# 2_interface.net
KiCad netlist of a schematic drawn in Altium Designer
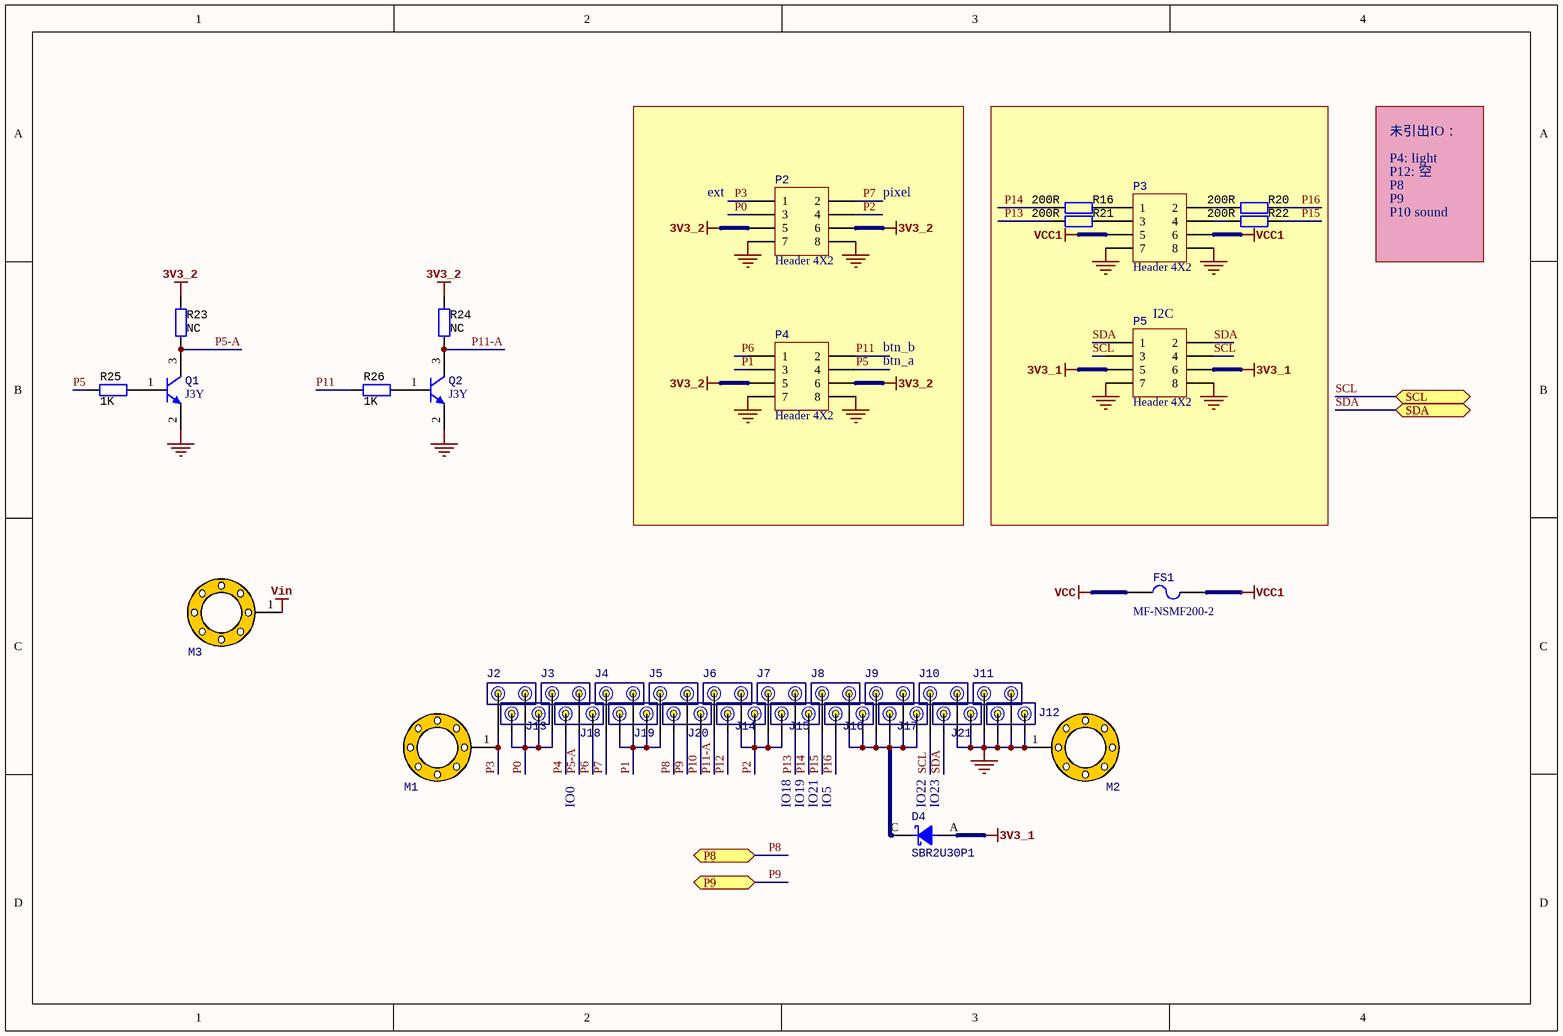
[diagram p0: 2.interface.SchDoc]

(export (version "E")
  (design (tool "Eeschema 10.0.6"))
  (components
    (comp (ref "D4")
      (value "SBR2U30P1")
      (footprint "POWERDI123")
      (fields (field (name "PARTNUMBER") "?") (field (name "PUBLISHER") "Altium Limited"))
      (libsource (lib "03.常用器件") (part "Diode_Schottky"))
    )
    (comp (ref "FS1")
      (value "MF-NSMF200-2")
      (footprint "R1206")
      (description "保险管")
      (libsource (lib "Miscellaneous Devices") (part "电子保险丝"))
    )
    (comp (ref "J2") (value "~") (footprint "顶针座子（2.54MM）") (libsource (lib "Schlib1") (part "pogopin")))
    (comp (ref "J3") (value "~") (footprint "顶针座子（2.54MM）") (libsource (lib "Schlib1") (part "pogopin")))
    (comp (ref "J4") (value "~") (footprint "顶针座子（2.54MM）") (libsource (lib "Schlib1") (part "pogopin")))
    (comp (ref "J5") (value "~") (footprint "顶针座子（2.54MM）") (libsource (lib "Schlib1") (part "pogopin")))
    (comp (ref "J6") (value "~") (footprint "顶针座子（2.54MM）") (libsource (lib "Schlib1") (part "pogopin")))
    (comp (ref "J7") (value "~") (footprint "顶针座子（2.54MM）") (libsource (lib "Schlib1") (part "pogopin")))
    (comp (ref "J8") (value "~") (footprint "顶针座子（2.54MM）") (libsource (lib "Schlib1") (part "pogopin")))
    (comp (ref "J9") (value "~") (footprint "顶针座子（2.54MM）") (libsource (lib "Schlib1") (part "pogopin")))
    (comp (ref "J10") (value "~") (footprint "顶针座子（2.54MM）") (libsource (lib "Schlib1") (part "pogopin")))
    (comp (ref "J11") (value "~") (footprint "顶针座子（2.54MM）") (libsource (lib "Schlib1") (part "pogopin")))
    (comp (ref "J12") (value "~") (footprint "顶针座子（2.54MM）") (libsource (lib "Schlib1") (part "pogopin_32")))
    (comp (ref "J13") (value "~") (footprint "顶针座子（2.54MM）") (libsource (lib "Schlib1") (part "pogopin_32")))
    (comp (ref "J14") (value "~") (footprint "顶针座子（2.54MM）") (libsource (lib "Schlib1") (part "pogopin_32")))
    (comp (ref "J15") (value "~") (footprint "顶针座子（2.54MM）") (libsource (lib "Schlib1") (part "pogopin_32")))
    (comp (ref "J16") (value "~") (footprint "顶针座子（2.54MM）") (libsource (lib "Schlib1") (part "pogopin_32")))
    (comp (ref "J17") (value "~") (footprint "顶针座子（2.54MM）") (libsource (lib "Schlib1") (part "pogopin_32")))
    (comp (ref "J18") (value "~") (footprint "顶针座子（2.54MM）") (libsource (lib "Schlib1") (part "pogopin_32")))
    (comp (ref "J19") (value "~") (footprint "顶针座子（2.54MM）") (libsource (lib "Schlib1") (part "pogopin_32")))
    (comp (ref "J20") (value "~") (footprint "顶针座子（2.54MM）") (libsource (lib "Schlib1") (part "pogopin_32")))
    (comp (ref "J21") (value "~") (footprint "顶针座子（2.54MM）") (libsource (lib "Schlib1") (part "pogopin_32")))
    (comp (ref "M1") (value "~") (footprint "3MM螺丝孔") (libsource (lib "labplus-connector") (part "screw")))
    (comp (ref "M2") (value "~") (footprint "3MM螺丝孔") (libsource (lib "labplus-connector") (part "screw")))
    (comp (ref "M3") (value "~") (footprint "3MM螺丝孔") (libsource (lib "labplus-connector") (part "screw")))
    (comp (ref "P2")
      (value "Header 4X2")
      (footprint "HDR2X4")
      (description "Header, 4-Pin, Dual row")
      (fields (field (name "PUBLISHER") "Altium Limited"))
      (libsource (lib "Miscellaneous Connectors") (part "Header 4X2"))
    )
    (comp (ref "P3")
      (value "Header 4X2")
      (footprint "HDR2X4")
      (description "Header, 4-Pin, Dual row")
      (fields (field (name "PUBLISHER") "Altium Limited"))
      (libsource (lib "Miscellaneous Connectors") (part "Header 4X2"))
    )
    (comp (ref "P4")
      (value "Header 4X2")
      (footprint "HDR2X4")
      (description "Header, 4-Pin, Dual row")
      (fields (field (name "PUBLISHER") "Altium Limited"))
      (libsource (lib "Miscellaneous Connectors") (part "Header 4X2"))
    )
    (comp (ref "P5")
      (value "Header 4X2")
      (footprint "HDR2X4")
      (description "Header, 4-Pin, Dual row")
      (fields (field (name "PUBLISHER") "Altium Limited"))
      (libsource (lib "Miscellaneous Connectors") (part "Header 4X2"))
    )
    (comp (ref "Q1")
      (value "J3Y")
      (footprint "DFN 3L")
      (description "NPN General Purpose Amplifier")
      (fields (field (name "PUBLISHER") "Altium Limited"))
      (libsource (lib "Schlib1") (part "2N3904"))
    )
    (comp (ref "Q2")
      (value "J3Y")
      (footprint "DFN 3L")
      (description "NPN General Purpose Amplifier")
      (fields (field (name "PUBLISHER") "Altium Limited"))
      (libsource (lib "Schlib1") (part "2N3904"))
    )
    (comp (ref "R16")
      (value "200R")
      (footprint "0402")
      (description "RES, 1.0k ohm, 5%, 0.1W, 0603")
      (fields
        (field (name "PARTNUMBER") "RC0603JR-071KL")
        (field (name "MANUFACTURER") "Yageo America")
        (field (name "PUBLISHER") "Texas Instruments")
      )
      (libsource (lib "") (part "RES1_1"))
    )
    (comp (ref "R20")
      (value "200R")
      (footprint "0402")
      (description "RES, 1.0k ohm, 5%, 0.1W, 0603")
      (fields
        (field (name "PARTNUMBER") "RC0603JR-071KL")
        (field (name "MANUFACTURER") "Yageo America")
        (field (name "PUBLISHER") "Texas Instruments")
      )
      (libsource (lib "") (part "RES1_1"))
    )
    (comp (ref "R21")
      (value "200R")
      (footprint "0402")
      (description "RES, 1.0k ohm, 5%, 0.1W, 0603")
      (fields
        (field (name "PARTNUMBER") "RC0603JR-071KL")
        (field (name "MANUFACTURER") "Yageo America")
        (field (name "PUBLISHER") "Texas Instruments")
      )
      (libsource (lib "") (part "RES1_1"))
    )
    (comp (ref "R22")
      (value "200R")
      (footprint "0402")
      (description "RES, 1.0k ohm, 5%, 0.1W, 0603")
      (fields
        (field (name "PARTNUMBER") "RC0603JR-071KL")
        (field (name "MANUFACTURER") "Yageo America")
        (field (name "PUBLISHER") "Texas Instruments")
      )
      (libsource (lib "") (part "RES1_1"))
    )
    (comp (ref "R23")
      (value "NC")
      (footprint "0402")
      (description "RES, 1.0k ohm, 5%, 0.1W, 0603")
      (fields
        (field (name "PARTNUMBER") "RC0603JR-071KL")
        (field (name "MANUFACTURER") "Yageo America")
        (field (name "PUBLISHER") "Texas Instruments")
      )
      (libsource (lib "03.常用器件") (part "RES1"))
    )
    (comp (ref "R24")
      (value "NC")
      (footprint "0402")
      (description "RES, 1.0k ohm, 5%, 0.1W, 0603")
      (fields
        (field (name "PARTNUMBER") "RC0603JR-071KL")
        (field (name "MANUFACTURER") "Yageo America")
        (field (name "PUBLISHER") "Texas Instruments")
      )
      (libsource (lib "03.常用器件") (part "RES1"))
    )
    (comp (ref "R25")
      (value "1K")
      (footprint "0402")
      (description "RES, 1.0k ohm, 5%, 0.1W, 0603")
      (fields
        (field (name "PARTNUMBER") "RC0603JR-071KL")
        (field (name "MANUFACTURER") "Yageo America")
        (field (name "PUBLISHER") "Texas Instruments")
      )
      (libsource (lib "") (part "RES1_2"))
    )
    (comp (ref "R26")
      (value "1K")
      (footprint "0402")
      (description "RES, 1.0k ohm, 5%, 0.1W, 0603")
      (fields
        (field (name "PARTNUMBER") "RC0603JR-071KL")
        (field (name "MANUFACTURER") "Yageo America")
        (field (name "PUBLISHER") "Texas Instruments")
      )
      (libsource (lib "") (part "RES1_2"))
    )
  )
  (nets
    (net (code "1") (name "/P0") (class "Default")
      (node (ref "J13") (pin "1") (pinfunction "1_1") (pintype "passive"))
      (node (ref "J13") (pin "2") (pinfunction "2_2") (pintype "passive"))
      (node (ref "J2") (pin "2") (pinfunction "2_2") (pintype "passive"))
      (node (ref "J3") (pin "1") (pinfunction "1_1") (pintype "passive"))
      (node (ref "P2") (pin "3") (pinfunction "3_3") (pintype "passive"))
    )
    (net (code "2") (name "/P1") (class "Default")
      (node (ref "J19") (pin "1") (pinfunction "1_1") (pintype "passive"))
      (node (ref "J19") (pin "2") (pinfunction "2_2") (pintype "passive"))
      (node (ref "J4") (pin "2") (pinfunction "2_2") (pintype "passive"))
      (node (ref "J5") (pin "1") (pinfunction "1_1") (pintype "passive"))
      (node (ref "P4") (pin "3") (pinfunction "3_3") (pintype "passive"))
    )
    (net (code "3") (name "/P2") (class "Default")
      (node (ref "J14") (pin "2") (pinfunction "2_2") (pintype "passive"))
      (node (ref "J15") (pin "1") (pinfunction "1_1") (pintype "passive"))
      (node (ref "J6") (pin "2") (pinfunction "2_2") (pintype "passive"))
      (node (ref "J7") (pin "1") (pinfunction "1_1") (pintype "passive"))
      (node (ref "P2") (pin "4") (pinfunction "4_4") (pintype "passive"))
    )
    (net (code "4") (name "/P3") (class "Default")
      (node (ref "J2") (pin "1") (pinfunction "1_1") (pintype "passive"))
      (node (ref "M1") (pin "1") (pinfunction "1_1") (pintype "passive"))
      (node (ref "P2") (pin "1") (pinfunction "1_1") (pintype "passive"))
    )
    (net (code "5") (name "/P4") (class "Default")
      (node (ref "J18") (pin "1") (pinfunction "1_1") (pintype "passive"))
    )
    (net (code "6") (name "/P5") (class "Default")
      (node (ref "P4") (pin "4") (pinfunction "4_4") (pintype "passive"))
      (node (ref "R25") (pin "1") (pinfunction "1_1") (pintype "passive"))
    )
    (net (code "7") (name "/P5-A") (class "Default")
      (node (ref "J3") (pin "2") (pinfunction "2_2") (pintype "passive"))
      (node (ref "Q1") (pin "3") (pinfunction "C_3") (pintype "passive"))
      (node (ref "R23") (pin "2") (pinfunction "2_2") (pintype "passive"))
    )
    (net (code "8") (name "/P6") (class "Default")
      (node (ref "J18") (pin "2") (pinfunction "2_2") (pintype "passive"))
      (node (ref "P4") (pin "1") (pinfunction "1_1") (pintype "passive"))
    )
    (net (code "9") (name "/P7") (class "Default")
      (node (ref "J4") (pin "1") (pinfunction "1_1") (pintype "passive"))
      (node (ref "P2") (pin "2") (pinfunction "2_2") (pintype "passive"))
    )
    (net (code "10") (name "/P8") (class "Default")
      (node (ref "J20") (pin "1") (pinfunction "1_1") (pintype "passive"))
    )
    (net (code "11") (name "/P9") (class "Default")
      (node (ref "J5") (pin "2") (pinfunction "2_2") (pintype "passive"))
    )
    (net (code "12") (name "/P10") (class "Default")
      (node (ref "J20") (pin "2") (pinfunction "2_2") (pintype "passive"))
    )
    (net (code "13") (name "/P11") (class "Default")
      (node (ref "P4") (pin "2") (pinfunction "2_2") (pintype "passive"))
      (node (ref "R26") (pin "1") (pinfunction "1_1") (pintype "passive"))
    )
    (net (code "14") (name "/P11-A") (class "Default")
      (node (ref "J6") (pin "1") (pinfunction "1_1") (pintype "passive"))
      (node (ref "Q2") (pin "3") (pinfunction "C_3") (pintype "passive"))
      (node (ref "R24") (pin "2") (pinfunction "2_2") (pintype "passive"))
    )
    (net (code "15") (name "/P12") (class "Default")
      (node (ref "J14") (pin "1") (pinfunction "1_1") (pintype "passive"))
    )
    (net (code "16") (name "/P13") (class "Default")
      (node (ref "J7") (pin "2") (pinfunction "2_2") (pintype "passive"))
      (node (ref "R21") (pin "1") (pinfunction "1_1") (pintype "passive"))
    )
    (net (code "17") (name "/P14") (class "Default")
      (node (ref "J15") (pin "2") (pinfunction "2_2") (pintype "passive"))
      (node (ref "R16") (pin "1") (pinfunction "1_1") (pintype "passive"))
    )
    (net (code "18") (name "/P15") (class "Default")
      (node (ref "J8") (pin "1") (pinfunction "1_1") (pintype "passive"))
      (node (ref "R22") (pin "2") (pinfunction "2_2") (pintype "passive"))
    )
    (net (code "19") (name "/P16") (class "Default")
      (node (ref "J16") (pin "1") (pinfunction "1_1") (pintype "passive"))
      (node (ref "R20") (pin "2") (pinfunction "2_2") (pintype "passive"))
    )
    (net (code "20") (name "/SCL") (class "Default")
      (node (ref "J10") (pin "1") (pinfunction "1_1") (pintype "passive"))
      (node (ref "P5") (pin "3") (pinfunction "3_3") (pintype "passive"))
      (node (ref "P5") (pin "4") (pinfunction "4_4") (pintype "passive"))
    )
    (net (code "21") (name "/SDA") (class "Default")
      (node (ref "J21") (pin "1") (pinfunction "1_1") (pintype "passive"))
      (node (ref "P5") (pin "1") (pinfunction "1_1") (pintype "passive"))
      (node (ref "P5") (pin "2") (pinfunction "2_2") (pintype "passive"))
    )
    (net (code "22") (name "3V3_1") (class "Default")
      (node (ref "D4") (pin "A") (pinfunction "ANODE_A") (pintype "passive"))
      (node (ref "P5") (pin "5") (pinfunction "5_5") (pintype "passive"))
      (node (ref "P5") (pin "6") (pinfunction "6_6") (pintype "passive"))
    )
    (net (code "23") (name "3V3_2") (class "Default")
      (node (ref "P2") (pin "5") (pinfunction "5_5") (pintype "passive"))
      (node (ref "P2") (pin "6") (pinfunction "6_6") (pintype "passive"))
      (node (ref "P4") (pin "5") (pinfunction "5_5") (pintype "passive"))
      (node (ref "P4") (pin "6") (pinfunction "6_6") (pintype "passive"))
      (node (ref "R23") (pin "1") (pinfunction "1_1") (pintype "passive"))
      (node (ref "R24") (pin "1") (pinfunction "1_1") (pintype "passive"))
    )
    (net (code "24") (name "<NO NET>") (class "Default")
      (node (ref "J10") (pin "2") (pinfunction "2_2") (pintype "passive"))
      (node (ref "J11") (pin "1") (pinfunction "1_1") (pintype "passive"))
      (node (ref "J11") (pin "2") (pinfunction "2_2") (pintype "passive"))
      (node (ref "J12") (pin "1") (pinfunction "1_1") (pintype "passive"))
      (node (ref "J12") (pin "2") (pinfunction "2_2") (pintype "passive"))
      (node (ref "J21") (pin "2") (pinfunction "2_2") (pintype "passive"))
      (node (ref "M2") (pin "1") (pinfunction "1_1") (pintype "passive"))
      (node (ref "P2") (pin "7") (pinfunction "7_7") (pintype "passive"))
      (node (ref "P2") (pin "8") (pinfunction "8_8") (pintype "passive"))
      (node (ref "P3") (pin "7") (pinfunction "7_7") (pintype "passive"))
      (node (ref "P3") (pin "8") (pinfunction "8_8") (pintype "passive"))
      (node (ref "P4") (pin "7") (pinfunction "7_7") (pintype "passive"))
      (node (ref "P4") (pin "8") (pinfunction "8_8") (pintype "passive"))
      (node (ref "P5") (pin "7") (pinfunction "7_7") (pintype "passive"))
      (node (ref "P5") (pin "8") (pinfunction "8_8") (pintype "passive"))
      (node (ref "Q1") (pin "2") (pinfunction "E_2") (pintype "passive"))
      (node (ref "Q2") (pin "2") (pinfunction "E_2") (pintype "passive"))
    )
    (net (code "25") (name "Net-(D4-CATHODE)") (class "Default")
      (node (ref "D4") (pin "C") (pinfunction "CATHODE_C") (pintype "passive"))
      (node (ref "J16") (pin "2") (pinfunction "2_2") (pintype "passive"))
      (node (ref "J17") (pin "1") (pinfunction "1_1") (pintype "passive"))
      (node (ref "J17") (pin "2") (pinfunction "2_2") (pintype "passive"))
      (node (ref "J8") (pin "2") (pinfunction "2_2") (pintype "passive"))
      (node (ref "J9") (pin "1") (pinfunction "1_1") (pintype "passive"))
      (node (ref "J9") (pin "2") (pinfunction "2_2") (pintype "passive"))
    )
    (net (code "26") (name "Net-(P3-Pad1)") (class "Default")
      (node (ref "P3") (pin "1") (pinfunction "1_1") (pintype "passive"))
      (node (ref "R16") (pin "2") (pinfunction "2_2") (pintype "passive"))
    )
    (net (code "27") (name "Net-(P3-Pad2)") (class "Default")
      (node (ref "P3") (pin "2") (pinfunction "2_2") (pintype "passive"))
      (node (ref "R20") (pin "1") (pinfunction "1_1") (pintype "passive"))
    )
    (net (code "28") (name "Net-(P3-Pad3)") (class "Default")
      (node (ref "P3") (pin "3") (pinfunction "3_3") (pintype "passive"))
      (node (ref "R21") (pin "2") (pinfunction "2_2") (pintype "passive"))
    )
    (net (code "29") (name "Net-(P3-Pad4)") (class "Default")
      (node (ref "P3") (pin "4") (pinfunction "4_4") (pintype "passive"))
      (node (ref "R22") (pin "1") (pinfunction "1_1") (pintype "passive"))
    )
    (net (code "30") (name "Net-(Q1-B)") (class "Default")
      (node (ref "Q1") (pin "1") (pinfunction "B_1") (pintype "passive"))
      (node (ref "R25") (pin "2") (pinfunction "2_2") (pintype "passive"))
    )
    (net (code "31") (name "Net-(Q2-B)") (class "Default")
      (node (ref "Q2") (pin "1") (pinfunction "B_1") (pintype "passive"))
      (node (ref "R26") (pin "2") (pinfunction "2_2") (pintype "passive"))
    )
    (net (code "32") (name "VCC") (class "Default")
      (node (ref "FS1") (pin "2") (pinfunction "1_2") (pintype "passive"))
    )
    (net (code "33") (name "VCC1") (class "Default")
      (node (ref "FS1") (pin "1") (pinfunction "0_1") (pintype "passive"))
      (node (ref "P3") (pin "5") (pinfunction "5_5") (pintype "passive"))
      (node (ref "P3") (pin "6") (pinfunction "6_6") (pintype "passive"))
    )
    (net (code "34") (name "Vin") (class "Default")
      (node (ref "M3") (pin "1") (pinfunction "1_1") (pintype "passive"))
    )
  )
)
